# Joy2PS2_rev2_2.net
KiCad netlist of a schematic drawn in EAGLE
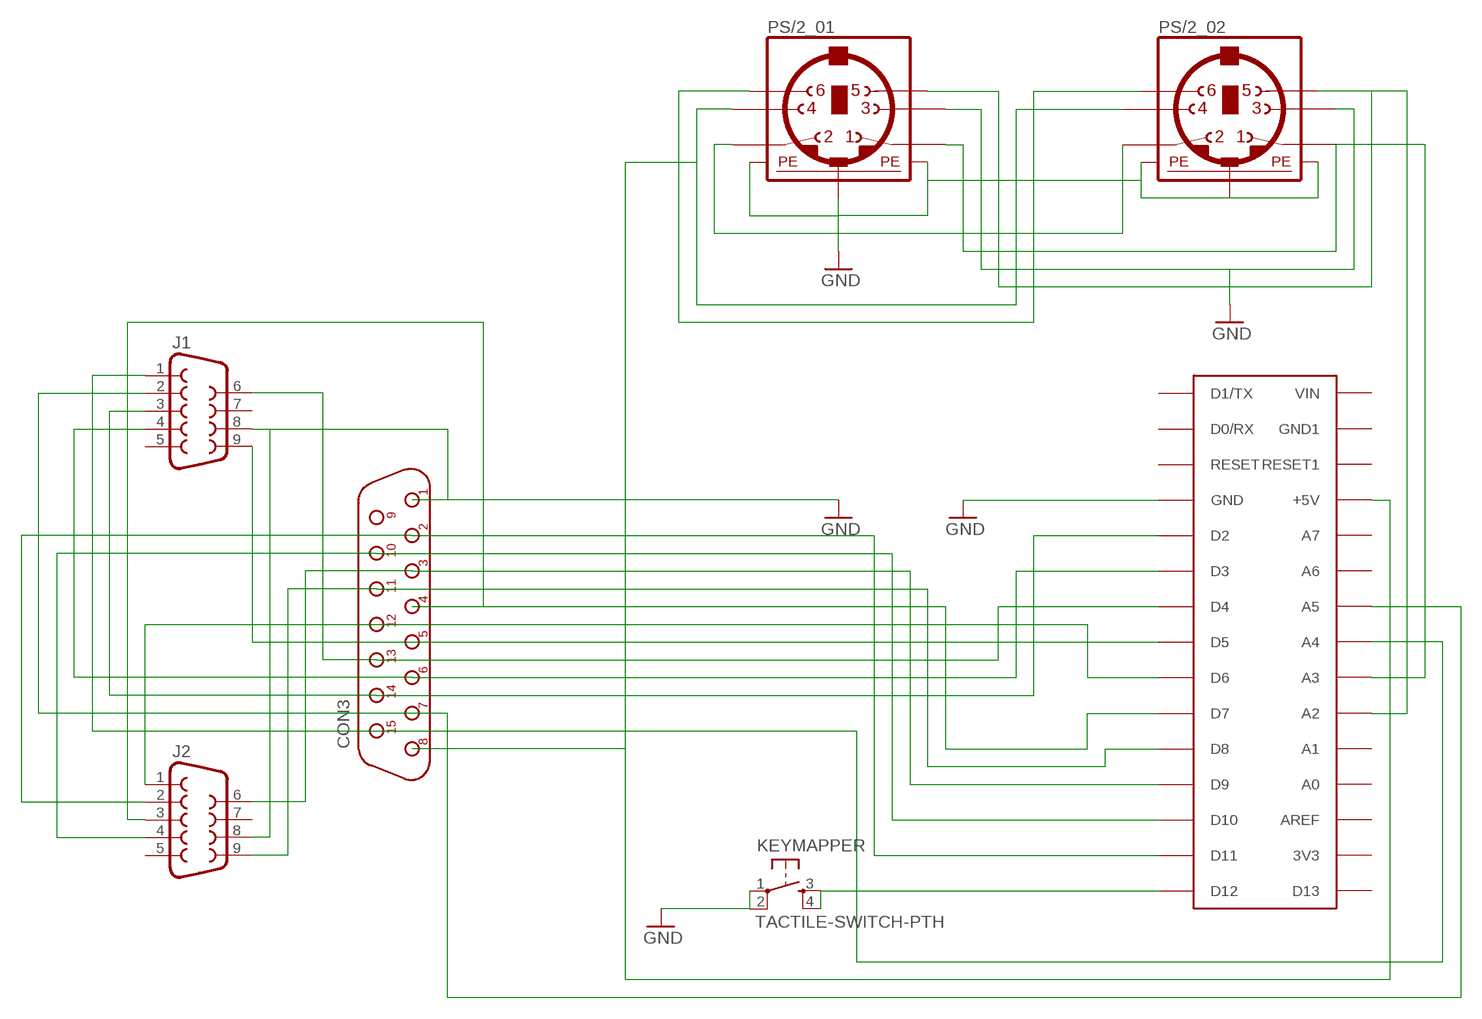
[diagram p0: schematic, sheet 1]

(export (version "E")
  (design (tool "Eeschema 10.0.6"))
  (components
    (comp (ref "ARDUINONANO")
      (value "ARDUINONANO")
      (footprint "eagle-import:PDIP-32")
      (libsource (lib "eagle-import") (part "ARDUINONANO"))
    )
    (comp (ref "CON3")
      (value "DB15M/90")
      (footprint "eagle-import:D-15M_90")
      (libsource (lib "eagle-import") (part "DB15M/90"))
    )
    (comp (ref "J1")
      (value "DB9MALE")
      (footprint "eagle-import:DB9_MALE")
      (libsource (lib "eagle-import") (part "DB9MALE"))
    )
    (comp (ref "J2")
      (value "DB9MALE")
      (footprint "eagle-import:DB9_MALE")
      (libsource (lib "eagle-import") (part "DB9MALE"))
    )
    (comp (ref "KEYMAPPER")
      (value "TACTILE-SWITCH-PTH")
      (footprint "eagle-import:TAC-SWITCH-PTH")
      (libsource (lib "eagle-import") (part "TACTILE-SWITCH-PTH"))
    )
    (comp (ref "PS/2_01")
      (value "MINI_DIN_6")
      (footprint "eagle-import:M_DIN6")
      (libsource (lib "eagle-import") (part "MINI_DIN_6"))
    )
    (comp (ref "PS/2_02")
      (value "MINI_DIN_6")
      (footprint "eagle-import:M_DIN6")
      (libsource (lib "eagle-import") (part "MINI_DIN_6"))
    )
  )
  (nets
    (net (code "1") (name "GND") (class "Default")
      (node (ref "ARDUINONANO") (pin "GND") (pinfunction "GND_GND") (pintype "bidirectional"))
      (node (ref "CON3") (pin "1") (pinfunction "1_1") (pintype "passive"))
      (node (ref "J1") (pin "8") (pinfunction "8_8") (pintype "passive"))
      (node (ref "J2") (pin "8") (pinfunction "8_8") (pintype "passive"))
      (node (ref "KEYMAPPER") (pin "1") (pinfunction "1_1") (pintype "passive"))
      (node (ref "KEYMAPPER") (pin "2") (pinfunction "2_2") (pintype "passive"))
      (node (ref "PS/2_01") (pin "3") (pinfunction "3_3") (pintype "passive"))
      (node (ref "PS/2_01") (pin "SH1") (pinfunction "PE1_SH1") (pintype "power_in"))
      (node (ref "PS/2_01") (pin "SH2") (pinfunction "PE2_SH2") (pintype "power_in"))
      (node (ref "PS/2_01") (pin "SH3") (pinfunction "PE3_SH3") (pintype "power_in"))
      (node (ref "PS/2_02") (pin "3") (pinfunction "3_3") (pintype "passive"))
      (node (ref "PS/2_02") (pin "SH1") (pinfunction "PE1_SH1") (pintype "power_in"))
      (node (ref "PS/2_02") (pin "SH2") (pinfunction "PE2_SH2") (pintype "power_in"))
      (node (ref "PS/2_02") (pin "SH3") (pinfunction "PE3_SH3") (pintype "power_in"))
    )
    (net (code "2") (name "Net-(ARDUINONANO-Pad+5V)") (class "Default")
      (node (ref "ARDUINONANO") (pin "+5V") (pinfunction "+5V_+5V") (pintype "bidirectional"))
      (node (ref "CON3") (pin "8") (pinfunction "8_8") (pintype "passive"))
      (node (ref "PS/2_01") (pin "4") (pinfunction "4_4") (pintype "passive"))
      (node (ref "PS/2_02") (pin "4") (pinfunction "4_4") (pintype "passive"))
    )
    (net (code "3") (name "Net-(ARDUINONANO-PadA2)") (class "Default")
      (node (ref "ARDUINONANO") (pin "A2") (pinfunction "A2_A2") (pintype "bidirectional"))
      (node (ref "PS/2_01") (pin "5") (pinfunction "5_5") (pintype "passive"))
      (node (ref "PS/2_02") (pin "5") (pinfunction "5_5") (pintype "passive"))
    )
    (net (code "4") (name "Net-(ARDUINONANO-PadA3)") (class "Default")
      (node (ref "ARDUINONANO") (pin "A3") (pinfunction "A3_A3") (pintype "bidirectional"))
      (node (ref "PS/2_01") (pin "1") (pinfunction "1_1") (pintype "passive"))
      (node (ref "PS/2_02") (pin "1") (pinfunction "1_1") (pintype "passive"))
    )
    (net (code "5") (name "Net-(ARDUINONANO-PadA4)") (class "Default")
      (node (ref "ARDUINONANO") (pin "A4") (pinfunction "A4_A4") (pintype "bidirectional"))
      (node (ref "CON3") (pin "15") (pinfunction "15_15") (pintype "passive"))
      (node (ref "J1") (pin "1") (pinfunction "1_1") (pintype "passive"))
    )
    (net (code "6") (name "Net-(ARDUINONANO-PadA5)") (class "Default")
      (node (ref "ARDUINONANO") (pin "A5") (pinfunction "A5_A5") (pintype "bidirectional"))
      (node (ref "CON3") (pin "7") (pinfunction "7_7") (pintype "passive"))
      (node (ref "J1") (pin "2") (pinfunction "2_2") (pintype "passive"))
    )
    (net (code "7") (name "Net-(ARDUINONANO-PadD2)") (class "Default")
      (node (ref "ARDUINONANO") (pin "D2") (pinfunction "D2_D2") (pintype "bidirectional"))
      (node (ref "CON3") (pin "14") (pinfunction "14_14") (pintype "passive"))
      (node (ref "J1") (pin "3") (pinfunction "3_3") (pintype "passive"))
    )
    (net (code "8") (name "Net-(ARDUINONANO-PadD3)") (class "Default")
      (node (ref "ARDUINONANO") (pin "D3") (pinfunction "D3_D3") (pintype "bidirectional"))
      (node (ref "CON3") (pin "6") (pinfunction "6_6") (pintype "passive"))
      (node (ref "J1") (pin "4") (pinfunction "4_4") (pintype "passive"))
    )
    (net (code "9") (name "Net-(ARDUINONANO-PadD4)") (class "Default")
      (node (ref "ARDUINONANO") (pin "D4") (pinfunction "D4_D4") (pintype "bidirectional"))
      (node (ref "CON3") (pin "13") (pinfunction "13_13") (pintype "passive"))
      (node (ref "J1") (pin "6") (pinfunction "6_6") (pintype "passive"))
    )
    (net (code "10") (name "Net-(ARDUINONANO-PadD5)") (class "Default")
      (node (ref "ARDUINONANO") (pin "D5") (pinfunction "D5_D5") (pintype "bidirectional"))
      (node (ref "CON3") (pin "5") (pinfunction "5_5") (pintype "passive"))
      (node (ref "J1") (pin "9") (pinfunction "9_9") (pintype "passive"))
    )
    (net (code "11") (name "Net-(ARDUINONANO-PadD6)") (class "Default")
      (node (ref "ARDUINONANO") (pin "D6") (pinfunction "D6_D6") (pintype "bidirectional"))
      (node (ref "CON3") (pin "12") (pinfunction "12_12") (pintype "passive"))
      (node (ref "J2") (pin "1") (pinfunction "1_1") (pintype "passive"))
    )
    (net (code "12") (name "Net-(ARDUINONANO-PadD7)") (class "Default")
      (node (ref "ARDUINONANO") (pin "D7") (pinfunction "D7_D7") (pintype "bidirectional"))
      (node (ref "CON3") (pin "4") (pinfunction "4_4") (pintype "passive"))
      (node (ref "J2") (pin "3") (pinfunction "3_3") (pintype "passive"))
    )
    (net (code "13") (name "Net-(ARDUINONANO-PadD8)") (class "Default")
      (node (ref "ARDUINONANO") (pin "D8") (pinfunction "D8_D8") (pintype "bidirectional"))
      (node (ref "CON3") (pin "11") (pinfunction "11_11") (pintype "passive"))
      (node (ref "J2") (pin "9") (pinfunction "9_9") (pintype "passive"))
    )
    (net (code "14") (name "Net-(ARDUINONANO-PadD9)") (class "Default")
      (node (ref "ARDUINONANO") (pin "D9") (pinfunction "D9_D9") (pintype "bidirectional"))
      (node (ref "CON3") (pin "3") (pinfunction "3_3") (pintype "passive"))
      (node (ref "J2") (pin "6") (pinfunction "6_6") (pintype "passive"))
    )
    (net (code "15") (name "Net-(ARDUINONANO-PadD10)") (class "Default")
      (node (ref "ARDUINONANO") (pin "D10") (pinfunction "D10_D10") (pintype "bidirectional"))
      (node (ref "CON3") (pin "10") (pinfunction "10_10") (pintype "passive"))
      (node (ref "J2") (pin "4") (pinfunction "4_4") (pintype "passive"))
    )
    (net (code "16") (name "Net-(ARDUINONANO-PadD11)") (class "Default")
      (node (ref "ARDUINONANO") (pin "D11") (pinfunction "D11_D11") (pintype "bidirectional"))
      (node (ref "CON3") (pin "2") (pinfunction "2_2") (pintype "passive"))
      (node (ref "J2") (pin "2") (pinfunction "2_2") (pintype "passive"))
    )
    (net (code "17") (name "Net-(ARDUINONANO-PadD12)") (class "Default")
      (node (ref "ARDUINONANO") (pin "D12") (pinfunction "D12_D12") (pintype "bidirectional"))
      (node (ref "KEYMAPPER") (pin "3") (pinfunction "3_3") (pintype "passive"))
      (node (ref "KEYMAPPER") (pin "4") (pinfunction "4_4") (pintype "passive"))
    )
    (net (code "18") (name "Net-(PS/2_01-Pad2)") (class "Default")
      (node (ref "PS/2_01") (pin "2") (pinfunction "2_2") (pintype "passive"))
      (node (ref "PS/2_02") (pin "2") (pinfunction "2_2") (pintype "passive"))
    )
    (net (code "19") (name "Net-(PS/2_01-Pad6)") (class "Default")
      (node (ref "PS/2_01") (pin "6") (pinfunction "6_6") (pintype "passive"))
      (node (ref "PS/2_02") (pin "6") (pinfunction "6_6") (pintype "passive"))
    )
    (net (code "20") (name "unconnected-(ARDUINONANO-Pad3V3)") (class "Default")
      (node (ref "ARDUINONANO") (pin "3V3") (pinfunction "3V3_3V3") (pintype "bidirectional"))
    )
    (net (code "21") (name "unconnected-(ARDUINONANO-PadA0)") (class "Default")
      (node (ref "ARDUINONANO") (pin "A0") (pinfunction "A0_A0") (pintype "bidirectional"))
    )
    (net (code "22") (name "unconnected-(ARDUINONANO-PadA1)") (class "Default")
      (node (ref "ARDUINONANO") (pin "A1") (pinfunction "A1_A1") (pintype "bidirectional"))
    )
    (net (code "23") (name "unconnected-(ARDUINONANO-PadA6)") (class "Default")
      (node (ref "ARDUINONANO") (pin "A6") (pinfunction "A6_A6") (pintype "bidirectional"))
    )
    (net (code "24") (name "unconnected-(ARDUINONANO-PadA7)") (class "Default")
      (node (ref "ARDUINONANO") (pin "A7") (pinfunction "A7_A7") (pintype "bidirectional"))
    )
    (net (code "25") (name "unconnected-(ARDUINONANO-PadAREF)") (class "Default")
      (node (ref "ARDUINONANO") (pin "AREF") (pinfunction "AREF_AREF") (pintype "bidirectional"))
    )
    (net (code "26") (name "unconnected-(ARDUINONANO-PadD0{slash}RX)") (class "Default")
      (node (ref "ARDUINONANO") (pin "D0/RX") (pinfunction "D0/RX_D0/RX") (pintype "bidirectional"))
    )
    (net (code "27") (name "unconnected-(ARDUINONANO-PadD1{slash}TX)") (class "Default")
      (node (ref "ARDUINONANO") (pin "D1/TX") (pinfunction "D1/TX_D1/TX") (pintype "bidirectional"))
    )
    (net (code "28") (name "unconnected-(ARDUINONANO-PadD13)") (class "Default")
      (node (ref "ARDUINONANO") (pin "D13") (pinfunction "D13_D13") (pintype "bidirectional"))
    )
    (net (code "29") (name "unconnected-(ARDUINONANO-PadGND1)") (class "Default")
      (node (ref "ARDUINONANO") (pin "GND1") (pinfunction "GND1_GND1") (pintype "bidirectional"))
    )
    (net (code "30") (name "unconnected-(ARDUINONANO-PadRESET)") (class "Default")
      (node (ref "ARDUINONANO") (pin "RESET") (pinfunction "RESET_RESET") (pintype "bidirectional"))
    )
    (net (code "31") (name "unconnected-(ARDUINONANO-PadRESET1)") (class "Default")
      (node (ref "ARDUINONANO") (pin "RESET1") (pinfunction "RESET1_RESET1") (pintype "bidirectional"))
    )
    (net (code "32") (name "unconnected-(ARDUINONANO-PadVIN)") (class "Default")
      (node (ref "ARDUINONANO") (pin "VIN") (pinfunction "VIN_VIN") (pintype "bidirectional"))
    )
    (net (code "33") (name "unconnected-(CON3-Pad9)") (class "Default")
      (node (ref "CON3") (pin "9") (pinfunction "9_9") (pintype "passive"))
    )
    (net (code "34") (name "unconnected-(J1-Pad5)") (class "Default")
      (node (ref "J1") (pin "5") (pinfunction "5_5") (pintype "passive"))
    )
    (net (code "35") (name "unconnected-(J1-Pad7)") (class "Default")
      (node (ref "J1") (pin "7") (pinfunction "7_7") (pintype "passive"))
    )
    (net (code "36") (name "unconnected-(J2-Pad5)") (class "Default")
      (node (ref "J2") (pin "5") (pinfunction "5_5") (pintype "passive"))
    )
    (net (code "37") (name "unconnected-(J2-Pad7)") (class "Default")
      (node (ref "J2") (pin "7") (pinfunction "7_7") (pintype "passive"))
    )
  )
)
